# ArcadeRpiSmartShield_33_Pi_interface.net
KiCad netlist of a schematic drawn in Altium Designer
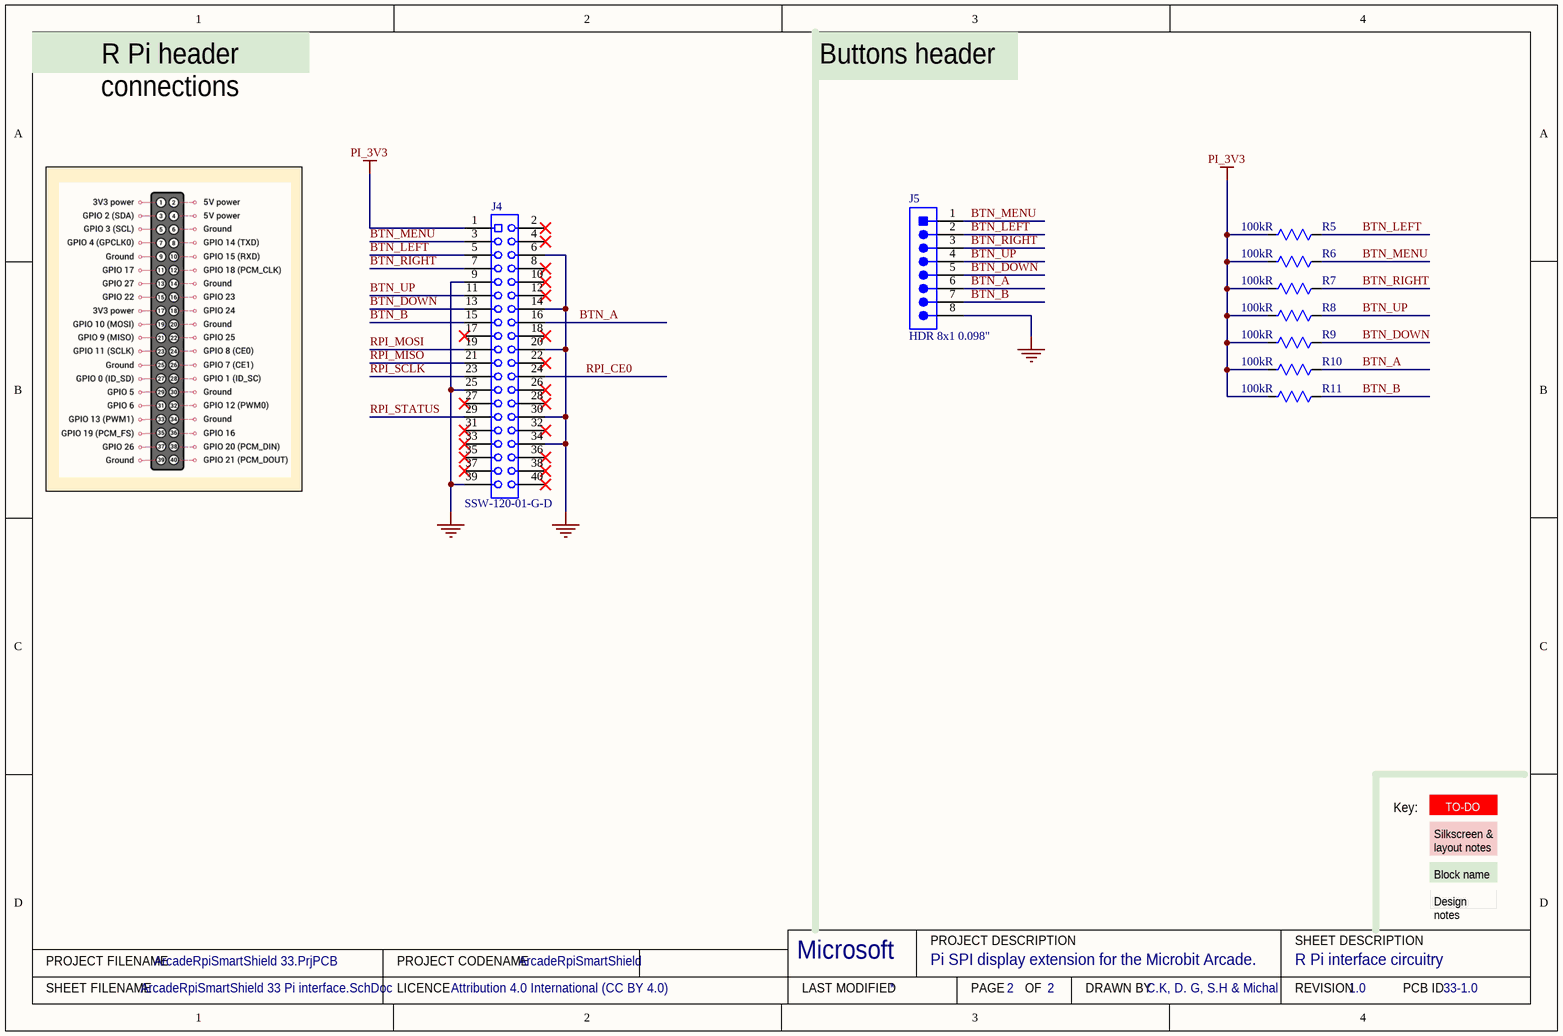
[diagram p0: ArcadeRpiSmartShield 33 Pi interface.SchDoc]

(export (version "E")
  (design (tool "Eeschema 10.0.6"))
  (components
    (comp (ref "J4")
      (value "SSW-120-01-G-D")
      (footprint "SAMTEC-SSW-120-01-G-D")
      (description "20 position 2 row (40 way) 0.1\" TH socket")
      (fields
        (field (name "MANUFACTURER") "Samtec")
        (field (name "MANUFACTURER PART NUMBER") "SSW-120-01-G-D")
      )
      (libsource (lib "Samtec") (part "SSW-120-01-G-D"))
    )
    (comp (ref "J5")
      (value "HDR 8x1 0.098\"")
      (footprint "B8B-XH-A(LF)(SN)")
      (description "CONN HEADER VERT 8POS 2.5MM")
      (fields
        (field (name "MANUFACTURER") "JST")
        (field (name "MANUFACTURER PART NUMBER") "B8B-XH-A(LF)(SN)")
        (field (name "CREATED BY") "D. Gakure")
        (field (name "CHECKED BY") "?")
      )
      (libsource (lib "JST") (part "B8B-XH-A(LF)(SN)"))
    )
    (comp (ref "R5")
      (value "RC0402FR-07100KL")
      (footprint "R0402 - Without outline")
      (description "RES SMD 100K OHM 1% 1/16W 0402")
      (fields
        (field (name "MANUFACTURER") "Yageo")
        (field (name "RESISTANCE") "100kR")
        (field (name "TOLERANCE") "1%")
        (field (name "CREATED BY") "DG")
        (field (name "CHECKED BY") "?")
      )
      (libsource (lib "Yageo") (part "RC0402FR-07100KL"))
    )
    (comp (ref "R6")
      (value "RC0402FR-07100KL")
      (footprint "R0402 - Without outline")
      (description "RES SMD 100K OHM 1% 1/16W 0402")
      (fields
        (field (name "MANUFACTURER") "Yageo")
        (field (name "RESISTANCE") "100kR")
        (field (name "TOLERANCE") "1%")
        (field (name "CREATED BY") "DG")
        (field (name "CHECKED BY") "?")
      )
      (libsource (lib "Yageo") (part "RC0402FR-07100KL"))
    )
    (comp (ref "R7")
      (value "RC0402FR-07100KL")
      (footprint "R0402 - Without outline")
      (description "RES SMD 100K OHM 1% 1/16W 0402")
      (fields
        (field (name "MANUFACTURER") "Yageo")
        (field (name "RESISTANCE") "100kR")
        (field (name "TOLERANCE") "1%")
        (field (name "CREATED BY") "DG")
        (field (name "CHECKED BY") "?")
      )
      (libsource (lib "Yageo") (part "RC0402FR-07100KL"))
    )
    (comp (ref "R8")
      (value "RC0402FR-07100KL")
      (footprint "R0402 - Without outline")
      (description "RES SMD 100K OHM 1% 1/16W 0402")
      (fields
        (field (name "MANUFACTURER") "Yageo")
        (field (name "RESISTANCE") "100kR")
        (field (name "TOLERANCE") "1%")
        (field (name "CREATED BY") "DG")
        (field (name "CHECKED BY") "?")
      )
      (libsource (lib "Yageo") (part "RC0402FR-07100KL"))
    )
    (comp (ref "R9")
      (value "RC0402FR-07100KL")
      (footprint "R0402 - Without outline")
      (description "RES SMD 100K OHM 1% 1/16W 0402")
      (fields
        (field (name "MANUFACTURER") "Yageo")
        (field (name "RESISTANCE") "100kR")
        (field (name "TOLERANCE") "1%")
        (field (name "CREATED BY") "DG")
        (field (name "CHECKED BY") "?")
      )
      (libsource (lib "Yageo") (part "RC0402FR-07100KL"))
    )
    (comp (ref "R10")
      (value "RC0402FR-07100KL")
      (footprint "R0402 - Without outline")
      (description "RES SMD 100K OHM 1% 1/16W 0402")
      (fields
        (field (name "MANUFACTURER") "Yageo")
        (field (name "RESISTANCE") "100kR")
        (field (name "TOLERANCE") "1%")
        (field (name "CREATED BY") "DG")
        (field (name "CHECKED BY") "?")
      )
      (libsource (lib "Yageo") (part "RC0402FR-07100KL"))
    )
    (comp (ref "R11")
      (value "RC0402FR-07100KL")
      (footprint "R0402 - Without outline")
      (description "RES SMD 100K OHM 1% 1/16W 0402")
      (fields
        (field (name "MANUFACTURER") "Yageo")
        (field (name "RESISTANCE") "100kR")
        (field (name "TOLERANCE") "1%")
        (field (name "CREATED BY") "DG")
        (field (name "CHECKED BY") "?")
      )
      (libsource (lib "Yageo") (part "RC0402FR-07100KL"))
    )
  )
  (nets
    (net (code "1") (name "/BTN_A") (class "Default")
      (node (ref "J4") (pin "16") (pinfunction "16_16") (pintype "passive"))
      (node (ref "J5") (pin "6") (pinfunction "6_6") (pintype "passive"))
      (node (ref "R10") (pin "2") (pinfunction "2_2") (pintype "passive"))
    )
    (net (code "2") (name "/BTN_B") (class "Default")
      (node (ref "J4") (pin "15") (pinfunction "15_15") (pintype "passive"))
      (node (ref "J5") (pin "7") (pinfunction "7_7") (pintype "passive"))
      (node (ref "R11") (pin "2") (pinfunction "2_2") (pintype "passive"))
    )
    (net (code "3") (name "/BTN_DOWN") (class "Default")
      (node (ref "J4") (pin "13") (pinfunction "13_13") (pintype "passive"))
      (node (ref "J5") (pin "5") (pinfunction "5_5") (pintype "passive"))
      (node (ref "R9") (pin "2") (pinfunction "2_2") (pintype "passive"))
    )
    (net (code "4") (name "/BTN_LEFT") (class "Default")
      (node (ref "J4") (pin "5") (pinfunction "5_5") (pintype "passive"))
      (node (ref "J5") (pin "2") (pinfunction "2_2") (pintype "passive"))
      (node (ref "R5") (pin "2") (pinfunction "2_2") (pintype "passive"))
    )
    (net (code "5") (name "/BTN_MENU") (class "Default")
      (node (ref "J4") (pin "3") (pinfunction "3_3") (pintype "passive"))
      (node (ref "J5") (pin "1") (pinfunction "1_1") (pintype "passive"))
      (node (ref "R6") (pin "2") (pinfunction "2_2") (pintype "passive"))
    )
    (net (code "6") (name "/BTN_RIGHT") (class "Default")
      (node (ref "J4") (pin "7") (pinfunction "7_7") (pintype "passive"))
      (node (ref "J5") (pin "3") (pinfunction "3_3") (pintype "passive"))
      (node (ref "R7") (pin "2") (pinfunction "2_2") (pintype "passive"))
    )
    (net (code "7") (name "/BTN_UP") (class "Default")
      (node (ref "J4") (pin "11") (pinfunction "11_11") (pintype "passive"))
      (node (ref "J5") (pin "4") (pinfunction "4_4") (pintype "passive"))
      (node (ref "R8") (pin "2") (pinfunction "2_2") (pintype "passive"))
    )
    (net (code "8") (name "/RPI_CE0") (class "Default")
      (node (ref "J4") (pin "24") (pinfunction "24_24") (pintype "passive"))
    )
    (net (code "9") (name "/RPI_MISO") (class "Default")
      (node (ref "J4") (pin "21") (pinfunction "21_21") (pintype "passive"))
    )
    (net (code "10") (name "/RPI_MOSI") (class "Default")
      (node (ref "J4") (pin "19") (pinfunction "19_19") (pintype "passive"))
    )
    (net (code "11") (name "/RPI_SCLK") (class "Default")
      (node (ref "J4") (pin "23") (pinfunction "23_23") (pintype "passive"))
    )
    (net (code "12") (name "/RPI_STATUS") (class "Default")
      (node (ref "J4") (pin "29") (pinfunction "29_29") (pintype "passive"))
    )
    (net (code "13") (name "GND") (class "Default")
      (node (ref "J4") (pin "14") (pinfunction "14_14") (pintype "passive"))
      (node (ref "J4") (pin "20") (pinfunction "20_20") (pintype "passive"))
      (node (ref "J4") (pin "25") (pinfunction "25_25") (pintype "passive"))
      (node (ref "J4") (pin "30") (pinfunction "30_30") (pintype "passive"))
      (node (ref "J4") (pin "34") (pinfunction "34_34") (pintype "passive"))
      (node (ref "J4") (pin "39") (pinfunction "39_39") (pintype "passive"))
      (node (ref "J4") (pin "6") (pinfunction "6_6") (pintype "passive"))
      (node (ref "J4") (pin "9") (pinfunction "9_9") (pintype "passive"))
      (node (ref "J5") (pin "8") (pinfunction "8_8") (pintype "passive"))
    )
    (net (code "14") (name "PI_3V3") (class "Default")
      (node (ref "J4") (pin "1") (pinfunction "1_1") (pintype "passive"))
      (node (ref "R10") (pin "1") (pinfunction "1_1") (pintype "passive"))
      (node (ref "R11") (pin "1") (pinfunction "1_1") (pintype "passive"))
      (node (ref "R5") (pin "1") (pinfunction "1_1") (pintype "passive"))
      (node (ref "R6") (pin "1") (pinfunction "1_1") (pintype "passive"))
      (node (ref "R7") (pin "1") (pinfunction "1_1") (pintype "passive"))
      (node (ref "R8") (pin "1") (pinfunction "1_1") (pintype "passive"))
      (node (ref "R9") (pin "1") (pinfunction "1_1") (pintype "passive"))
    )
    (net (code "15") (name "unconnected-(J4-Pad2)") (class "Default")
      (node (ref "J4") (pin "2") (pinfunction "2_2") (pintype "passive+no_connect"))
    )
    (net (code "16") (name "unconnected-(J4-Pad4)") (class "Default")
      (node (ref "J4") (pin "4") (pinfunction "4_4") (pintype "passive+no_connect"))
    )
    (net (code "17") (name "unconnected-(J4-Pad8)") (class "Default")
      (node (ref "J4") (pin "8") (pinfunction "8_8") (pintype "passive+no_connect"))
    )
    (net (code "18") (name "unconnected-(J4-Pad10)") (class "Default")
      (node (ref "J4") (pin "10") (pinfunction "10_10") (pintype "passive+no_connect"))
    )
    (net (code "19") (name "unconnected-(J4-Pad12)") (class "Default")
      (node (ref "J4") (pin "12") (pinfunction "12_12") (pintype "passive+no_connect"))
    )
    (net (code "20") (name "unconnected-(J4-Pad17)") (class "Default")
      (node (ref "J4") (pin "17") (pinfunction "17_17") (pintype "passive+no_connect"))
    )
    (net (code "21") (name "unconnected-(J4-Pad18)") (class "Default")
      (node (ref "J4") (pin "18") (pinfunction "18_18") (pintype "passive+no_connect"))
    )
    (net (code "22") (name "unconnected-(J4-Pad22)") (class "Default")
      (node (ref "J4") (pin "22") (pinfunction "22_22") (pintype "passive+no_connect"))
    )
    (net (code "23") (name "unconnected-(J4-Pad26)") (class "Default")
      (node (ref "J4") (pin "26") (pinfunction "26_26") (pintype "passive+no_connect"))
    )
    (net (code "24") (name "unconnected-(J4-Pad27)") (class "Default")
      (node (ref "J4") (pin "27") (pinfunction "27_27") (pintype "passive+no_connect"))
    )
    (net (code "25") (name "unconnected-(J4-Pad28)") (class "Default")
      (node (ref "J4") (pin "28") (pinfunction "28_28") (pintype "passive+no_connect"))
    )
    (net (code "26") (name "unconnected-(J4-Pad31)") (class "Default")
      (node (ref "J4") (pin "31") (pinfunction "31_31") (pintype "passive+no_connect"))
    )
    (net (code "27") (name "unconnected-(J4-Pad32)") (class "Default")
      (node (ref "J4") (pin "32") (pinfunction "32_32") (pintype "passive+no_connect"))
    )
    (net (code "28") (name "unconnected-(J4-Pad33)") (class "Default")
      (node (ref "J4") (pin "33") (pinfunction "33_33") (pintype "passive+no_connect"))
    )
    (net (code "29") (name "unconnected-(J4-Pad35)") (class "Default")
      (node (ref "J4") (pin "35") (pinfunction "35_35") (pintype "passive+no_connect"))
    )
    (net (code "30") (name "unconnected-(J4-Pad36)") (class "Default")
      (node (ref "J4") (pin "36") (pinfunction "36_36") (pintype "passive+no_connect"))
    )
    (net (code "31") (name "unconnected-(J4-Pad37)") (class "Default")
      (node (ref "J4") (pin "37") (pinfunction "37_37") (pintype "passive+no_connect"))
    )
    (net (code "32") (name "unconnected-(J4-Pad38)") (class "Default")
      (node (ref "J4") (pin "38") (pinfunction "38_38") (pintype "passive+no_connect"))
    )
    (net (code "33") (name "unconnected-(J4-Pad40)") (class "Default")
      (node (ref "J4") (pin "40") (pinfunction "40_40") (pintype "passive+no_connect"))
    )
  )
)
